# FMB-MCU.net
KiCad netlist of a schematic drawn in Altium Designer
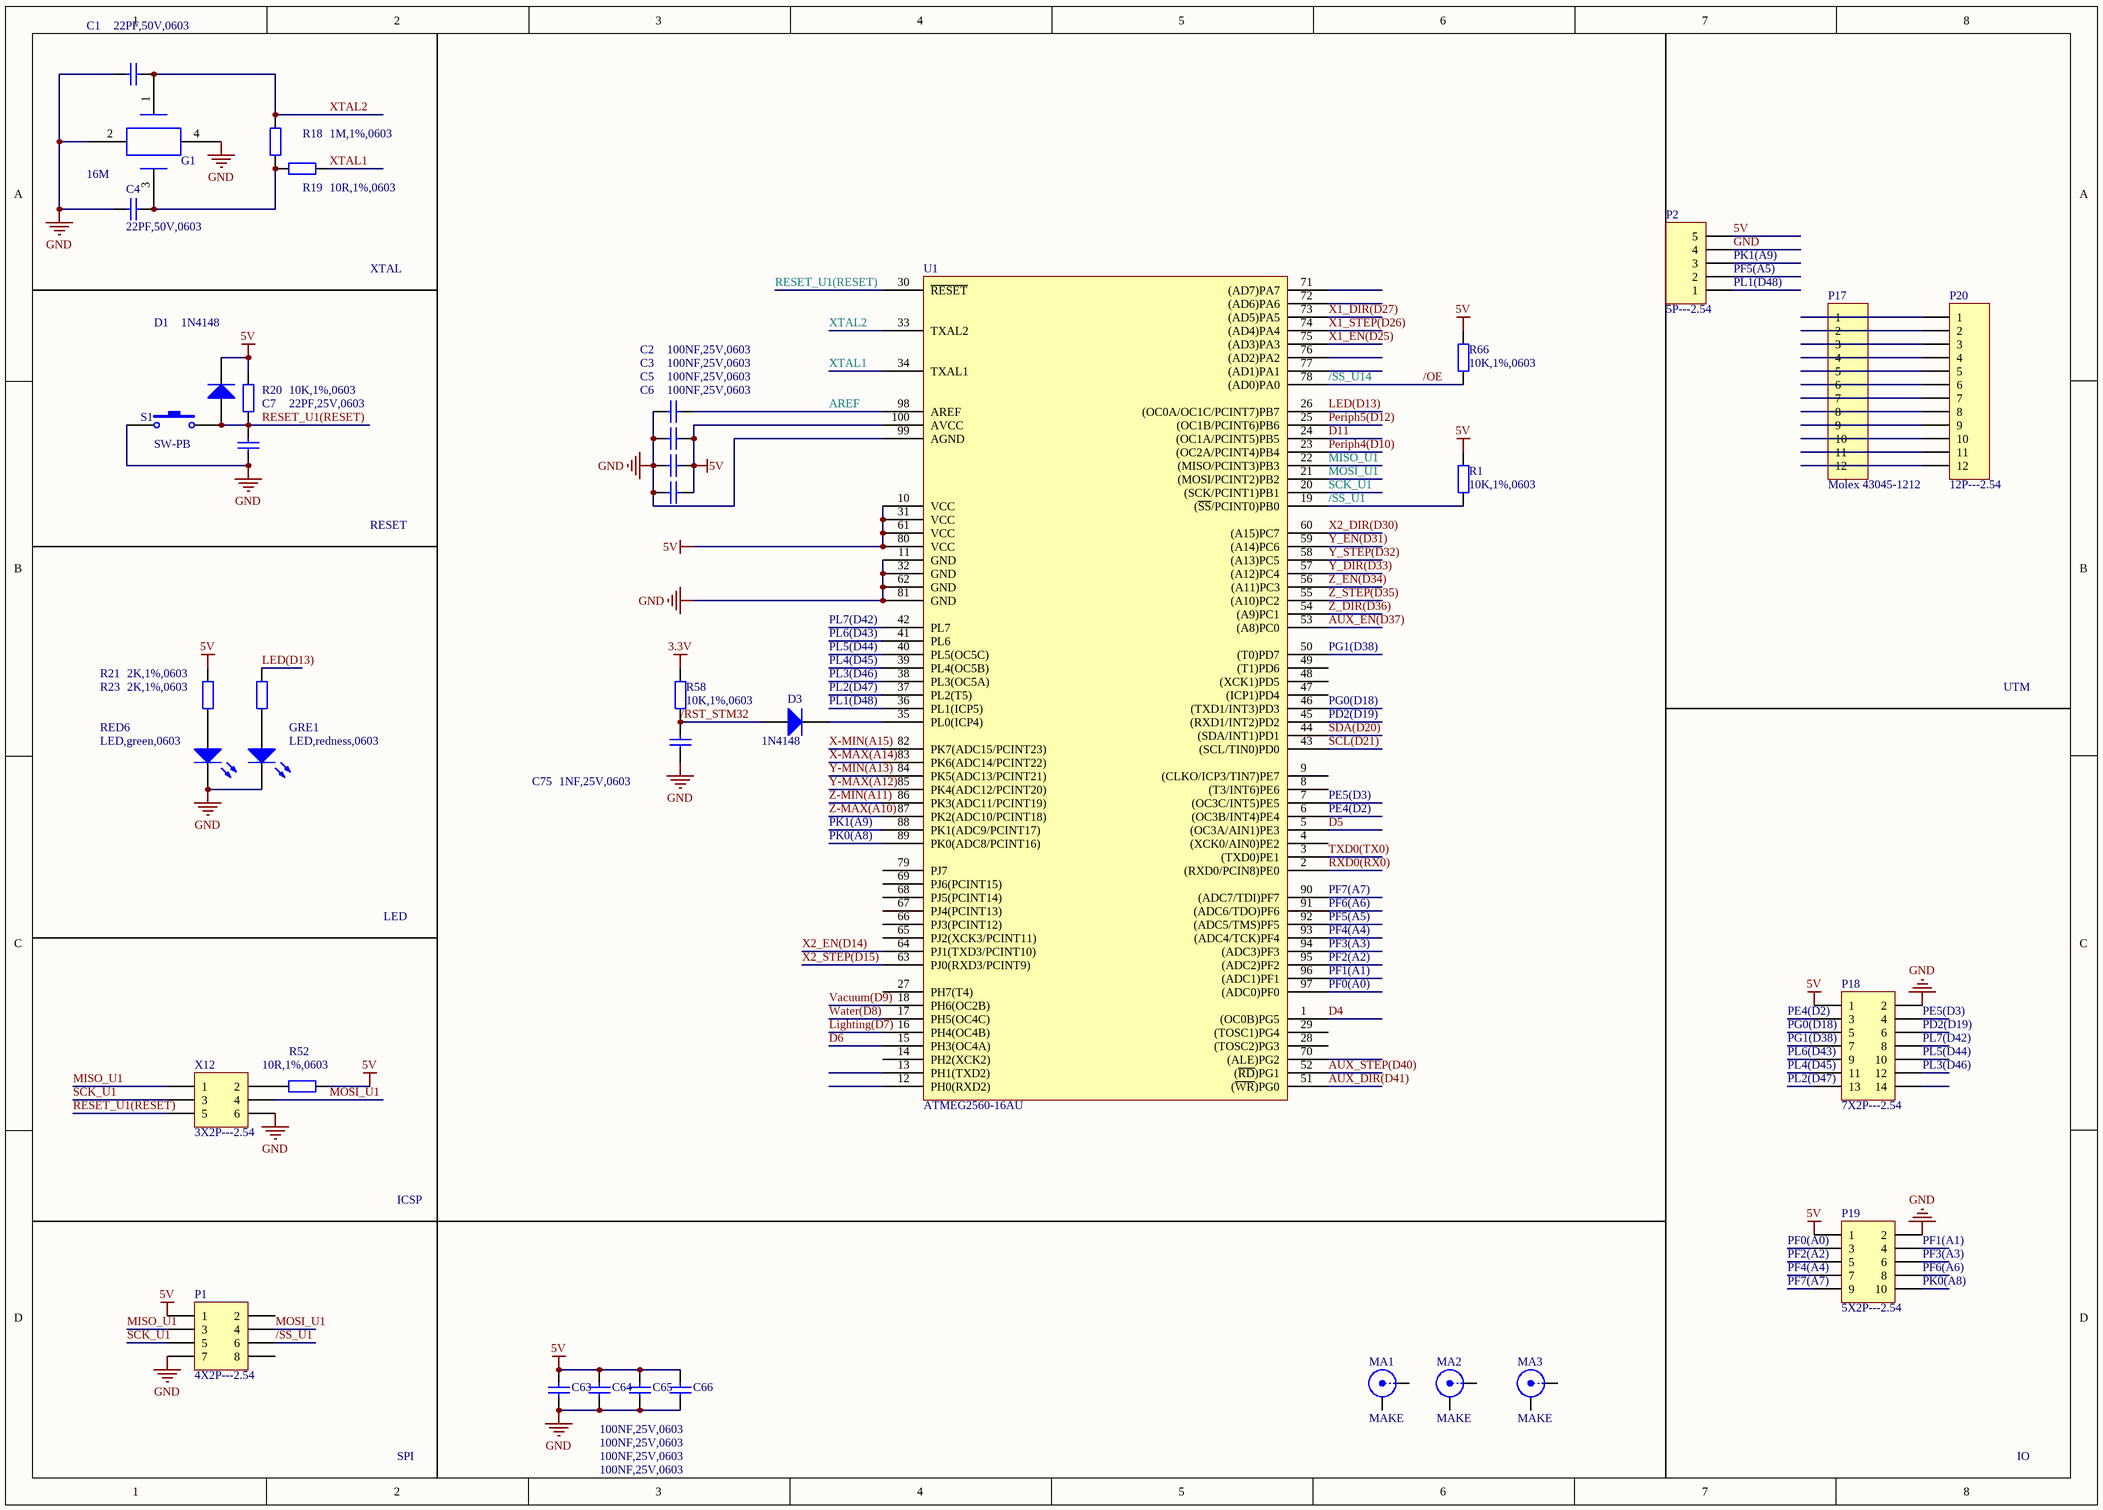
[diagram p0: FMB-MCU.SchDoc]

(export (version "E")
  (design (tool "Eeschema 10.0.6"))
  (components
    (comp (ref "C1")
      (value "22PF,50V,0603")
      (footprint "RC0603")
      (description "Capacitor")
      (fields (field (name "PUBLISHER") "Altium Limited"))
      (libsource (lib "Miscellaneous Devices") (part "Cap"))
    )
    (comp (ref "C2")
      (value "100NF,25V,0603")
      (footprint "RC0603")
      (description "Capacitor")
      (fields (field (name "PUBLISHER") "Altium Limited"))
      (libsource (lib "Miscellaneous Devices") (part "Cap"))
    )
    (comp (ref "C3")
      (value "100NF,25V,0603")
      (footprint "RC0603")
      (description "Capacitor")
      (fields (field (name "PUBLISHER") "Altium Limited"))
      (libsource (lib "Miscellaneous Devices") (part "Cap"))
    )
    (comp (ref "C4")
      (value "22PF,50V,0603")
      (footprint "RC0603")
      (description "Capacitor")
      (fields (field (name "PUBLISHER") "Altium Limited"))
      (libsource (lib "Miscellaneous Devices") (part "Cap"))
    )
    (comp (ref "C5")
      (value "100NF,25V,0603")
      (footprint "RC0603")
      (description "Capacitor")
      (fields (field (name "PUBLISHER") "Altium Limited"))
      (libsource (lib "Miscellaneous Devices") (part "Cap"))
    )
    (comp (ref "C6")
      (value "100NF,25V,0603")
      (footprint "RC0603")
      (description "Capacitor")
      (fields (field (name "PUBLISHER") "Altium Limited"))
      (libsource (lib "Miscellaneous Devices") (part "Cap"))
    )
    (comp (ref "C7")
      (value "22PF,25V,0603")
      (footprint "RC0603")
      (description "Capacitor")
      (fields (field (name "PUBLISHER") "Altium Limited"))
      (libsource (lib "Miscellaneous Devices") (part "Cap"))
    )
    (comp (ref "C63")
      (value "100NF,25V,0603")
      (footprint "RC0603")
      (description "Capacitor")
      (fields (field (name "PUBLISHER") "Altium Limited"))
      (libsource (lib "Miscellaneous Devices") (part "Cap"))
    )
    (comp (ref "C64")
      (value "100NF,25V,0603")
      (footprint "RC0603")
      (description "Capacitor")
      (fields (field (name "PUBLISHER") "Altium Limited"))
      (libsource (lib "Miscellaneous Devices") (part "Cap"))
    )
    (comp (ref "C65")
      (value "100NF,25V,0603")
      (footprint "RC0603")
      (description "Capacitor")
      (fields (field (name "PUBLISHER") "Altium Limited"))
      (libsource (lib "Miscellaneous Devices") (part "Cap"))
    )
    (comp (ref "C66")
      (value "100NF,25V,0603")
      (footprint "RC0603")
      (description "Capacitor")
      (fields (field (name "PUBLISHER") "Altium Limited"))
      (libsource (lib "Miscellaneous Devices") (part "Cap"))
    )
    (comp (ref "C75")
      (value "1NF,25V,0603")
      (footprint "RC0603")
      (description "Capacitor")
      (fields (field (name "PUBLISHER") "Altium Limited"))
      (libsource (lib "Miscellaneous Devices") (part "Cap"))
    )
    (comp (ref "D1")
      (value "1N4148")
      (footprint "SOD-323")
      (description "Default Diode")
      (fields (field (name "PUBLISHER") "Altium Limited"))
      (libsource (lib "Miscellaneous Devices") (part "Diode"))
    )
    (comp (ref "D3")
      (value "1N4148")
      (footprint "SOD-323")
      (description "Default Diode")
      (fields (field (name "PUBLISHER") "Altium Limited"))
      (libsource (lib "Miscellaneous Devices") (part "Diode"))
    )
    (comp (ref "G1") (value "16M") (footprint "Y-3225") (libsource (lib "STM32F407VE") (part "G")))
    (comp (ref "GRE1")
      (value "LED,redness,0603")
      (footprint "LED-0603")
      (description "Typical INFRARED GaAs LED")
      (fields (field (name "PUBLISHER") "Altium Limited"))
      (libsource (lib "Miscellaneous Devices") (part "LED0"))
    )
    (comp (ref "MA1")
      (value "MAKE")
      (description "BNC Elbow Connector")
      (fields (field (name "PUBLISHER") "Altium Limited"))
      (libsource (lib "Miscellaneous Connectors") (part "BNC"))
    )
    (comp (ref "MA2")
      (value "MAKE")
      (description "BNC Elbow Connector")
      (fields (field (name "PUBLISHER") "Altium Limited"))
      (libsource (lib "Miscellaneous Connectors") (part "BNC"))
    )
    (comp (ref "MA3")
      (value "MAKE")
      (description "BNC Elbow Connector")
      (fields (field (name "PUBLISHER") "Altium Limited"))
      (libsource (lib "Miscellaneous Connectors") (part "BNC"))
    )
    (comp (ref "P1")
      (value "4X2P---2.54")
      (footprint "HDR2X4")
      (description "Header, 4-Pin, Dual row")
      (fields (field (name "PUBLISHER") "Altium Limited"))
      (libsource (lib "Miscellaneous Connectors") (part "Header 4X2"))
    )
    (comp (ref "P2")
      (value "5P---2.54")
      (footprint "HDR1X5")
      (description "Header, 5-Pin")
      (fields (field (name "PUBLISHER") "Altium Limited"))
      (libsource (lib "Miscellaneous Connectors") (part "Header 5"))
    )
    (comp (ref "P17")
      (value "Molex 43045-1212")
      (footprint "43045-1212")
      (description "Header, 12-Pin")
      (fields (field (name "PUBLISHER") "Altium Limited"))
      (libsource (lib "Miscellaneous Connectors") (part "Header 12"))
    )
    (comp (ref "P18")
      (value "7X2P---2.54")
      (footprint "HDR2X7")
      (description "Header, 7-Pin, Dual row")
      (fields (field (name "PUBLISHER") "Altium Limited"))
      (libsource (lib "Miscellaneous Connectors") (part "Header 7X2"))
    )
    (comp (ref "P19")
      (value "5X2P---2.54")
      (footprint "HDR2X5")
      (description "Header, 5-Pin, Dual row")
      (fields (field (name "PUBLISHER") "Altium Limited"))
      (libsource (lib "Miscellaneous Connectors") (part "Header 5X2"))
    )
    (comp (ref "P20")
      (value "12P---2.54")
      (footprint "HDR1X12")
      (description "Header, 12-Pin")
      (fields (field (name "PUBLISHER") "Altium Limited"))
      (libsource (lib "Miscellaneous Connectors") (part "Header 12"))
    )
    (comp (ref "R1")
      (value "10K,1%,0603")
      (footprint "RC0603")
      (description "Resistor")
      (fields (field (name "PUBLISHER") "Altium Limited"))
      (libsource (lib "") (part "Res2_1"))
    )
    (comp (ref "R18")
      (value "1M,1%,0603")
      (footprint "RC0603")
      (description "Resistor")
      (fields (field (name "PUBLISHER") "Altium Limited"))
      (libsource (lib "Miscellaneous Devices") (part "Res2"))
    )
    (comp (ref "R19")
      (value "10R,1%,0603")
      (footprint "RC0603")
      (description "Resistor")
      (fields (field (name "PUBLISHER") "Altium Limited"))
      (libsource (lib "") (part "Res2_3"))
    )
    (comp (ref "R20")
      (value "10K,1%,0603")
      (footprint "RC0603")
      (description "Resistor")
      (fields (field (name "PUBLISHER") "Altium Limited"))
      (libsource (lib "Miscellaneous Devices") (part "Res2"))
    )
    (comp (ref "R21")
      (value "2K,1%,0603")
      (footprint "RC0603")
      (description "Resistor")
      (fields (field (name "PUBLISHER") "Altium Limited"))
      (libsource (lib "Miscellaneous Devices") (part "Res2"))
    )
    (comp (ref "R23")
      (value "2K,1%,0603")
      (footprint "RC0603")
      (description "Resistor")
      (fields (field (name "PUBLISHER") "Altium Limited"))
      (libsource (lib "Miscellaneous Devices") (part "Res2"))
    )
    (comp (ref "R52")
      (value "10R,1%,0603")
      (footprint "RC0603")
      (description "Resistor")
      (fields (field (name "PUBLISHER") "Altium Limited"))
      (libsource (lib "") (part "Res2_2"))
    )
    (comp (ref "R58")
      (value "10K,1%,0603")
      (footprint "RC0603")
      (description "Resistor")
      (fields (field (name "PUBLISHER") "Altium Limited"))
      (libsource (lib "Miscellaneous Devices") (part "Res2"))
    )
    (comp (ref "R66")
      (value "10K,1%,0603")
      (footprint "RC0603")
      (description "Resistor")
      (fields (field (name "PUBLISHER") "Altium Limited"))
      (libsource (lib "") (part "Res2_1"))
    )
    (comp (ref "RED6")
      (value "LED,green,0603")
      (footprint "LED-0603")
      (description "Typical INFRARED GaAs LED")
      (fields (field (name "PUBLISHER") "Altium Limited"))
      (libsource (lib "Miscellaneous Devices") (part "LED0"))
    )
    (comp (ref "S1")
      (value "SW-PB")
      (footprint "DIP6*6")
      (description "Switch")
      (fields (field (name "PUBLISHER") "Altium Limited"))
      (libsource (lib "Miscellaneous Devices") (part "SW-PB"))
    )
    (comp (ref "U1")
      (value "ATMEG2560-16AU")
      (footprint "LQFP-100")
      (libsource (lib "LDO原理图库") (part "ATMEG2560-16AU"))
    )
    (comp (ref "X12")
      (value "3X2P---2.54")
      (footprint "HDR2X3")
      (description "Header, 3-Pin, Dual row")
      (fields (field (name "PUBLISHER") "Altium Limited"))
      (libsource (lib "Miscellaneous Connectors") (part "Header 3X2"))
    )
  )
  (nets
    (net (code "1") (name "/AREF") (class "Default")
      (node (ref "C2") (pin "1") (pinfunction "1_1") (pintype "passive"))
      (node (ref "U1") (pin "98") (pinfunction "AREF_98") (pintype "passive"))
    )
    (net (code "2") (name "/AUX_DIR(D41)") (class "Default")
      (node (ref "U1") (pin "51") (pinfunction "(~{WR})PG0_51") (pintype "passive"))
    )
    (net (code "3") (name "/AUX_EN(D37)") (class "Default")
      (node (ref "U1") (pin "53") (pinfunction "(A8)PC0_53") (pintype "passive"))
    )
    (net (code "4") (name "/AUX_STEP(D40)") (class "Default")
      (node (ref "U1") (pin "52") (pinfunction "(~{RD})PG1_52") (pintype "passive"))
    )
    (net (code "5") (name "/D4") (class "Default")
      (node (ref "U1") (pin "1") (pinfunction "(OC0B)PG5_1") (pintype "passive"))
    )
    (net (code "6") (name "/D5") (class "Default")
      (node (ref "U1") (pin "5") (pinfunction "(OC3A/AIN1)PE3_5") (pintype "passive"))
    )
    (net (code "7") (name "/D6") (class "Default")
      (node (ref "U1") (pin "15") (pinfunction "PH3(OC4A)_15") (pintype "passive"))
    )
    (net (code "8") (name "/D11") (class "Default")
      (node (ref "U1") (pin "24") (pinfunction "(OC1A/PCINT5)PB5_24") (pintype "passive"))
    )
    (net (code "9") (name "/LED(D13)") (class "Default")
      (node (ref "R21") (pin "1") (pinfunction "1_1") (pintype "passive"))
      (node (ref "U1") (pin "26") (pinfunction "(OC0A/OC1C/PCINT7)PB7_26") (pintype "passive"))
    )
    (net (code "10") (name "/Lighting(D7)") (class "Default")
      (node (ref "U1") (pin "16") (pinfunction "PH4(OC4B)_16") (pintype "passive"))
    )
    (net (code "11") (name "/MISO_U1") (class "Default")
      (node (ref "P1") (pin "3") (pinfunction "3_3") (pintype "passive"))
      (node (ref "U1") (pin "22") (pinfunction "(MISO/PCINT3)PB3_22") (pintype "passive"))
      (node (ref "X12") (pin "1") (pinfunction "1_1") (pintype "passive"))
    )
    (net (code "12") (name "/MOSI_U1") (class "Default")
      (node (ref "P1") (pin "4") (pinfunction "4_4") (pintype "passive"))
      (node (ref "U1") (pin "21") (pinfunction "(MOSI/PCINT2)PB2_21") (pintype "passive"))
      (node (ref "X12") (pin "4") (pinfunction "4_4") (pintype "passive"))
    )
    (net (code "13") (name "/PD2(D19)") (class "Default")
      (node (ref "P18") (pin "6") (pinfunction "6_6") (pintype "passive"))
      (node (ref "U1") (pin "45") (pinfunction "(RXD1/INT2)PD2_45") (pintype "passive"))
    )
    (net (code "14") (name "/PE4(D2)") (class "Default")
      (node (ref "P18") (pin "3") (pinfunction "3_3") (pintype "passive"))
      (node (ref "U1") (pin "6") (pinfunction "(OC3B/INT4)PE4_6") (pintype "passive"))
    )
    (net (code "15") (name "/PE5(D3)") (class "Default")
      (node (ref "P18") (pin "4") (pinfunction "4_4") (pintype "passive"))
      (node (ref "U1") (pin "7") (pinfunction "(OC3C/INT5)PE5_7") (pintype "passive"))
    )
    (net (code "16") (name "/PF0(A0)") (class "Default")
      (node (ref "P19") (pin "3") (pinfunction "3_3") (pintype "passive"))
      (node (ref "U1") (pin "97") (pinfunction "(ADC0)PF0_97") (pintype "passive"))
    )
    (net (code "17") (name "/PF1(A1)") (class "Default")
      (node (ref "P19") (pin "4") (pinfunction "4_4") (pintype "passive"))
      (node (ref "U1") (pin "96") (pinfunction "(ADC1)PF1_96") (pintype "passive"))
    )
    (net (code "18") (name "/PF2(A2)") (class "Default")
      (node (ref "P19") (pin "5") (pinfunction "5_5") (pintype "passive"))
      (node (ref "U1") (pin "95") (pinfunction "(ADC2)PF2_95") (pintype "passive"))
    )
    (net (code "19") (name "/PF3(A3)") (class "Default")
      (node (ref "P19") (pin "6") (pinfunction "6_6") (pintype "passive"))
      (node (ref "U1") (pin "94") (pinfunction "(ADC3)PF3_94") (pintype "passive"))
    )
    (net (code "20") (name "/PF4(A4)") (class "Default")
      (node (ref "P19") (pin "7") (pinfunction "7_7") (pintype "passive"))
      (node (ref "U1") (pin "93") (pinfunction "(ADC4/TCK)PF4_93") (pintype "passive"))
    )
    (net (code "21") (name "/PF5(A5)") (class "Default")
      (node (ref "P2") (pin "2") (pinfunction "2_2") (pintype "passive"))
      (node (ref "U1") (pin "92") (pinfunction "(ADC5/TMS)PF5_92") (pintype "passive"))
    )
    (net (code "22") (name "/PF6(A6)") (class "Default")
      (node (ref "P19") (pin "8") (pinfunction "8_8") (pintype "passive"))
      (node (ref "U1") (pin "91") (pinfunction "(ADC6/TDO)PF6_91") (pintype "passive"))
    )
    (net (code "23") (name "/PF7(A7)") (class "Default")
      (node (ref "P19") (pin "9") (pinfunction "9_9") (pintype "passive"))
      (node (ref "U1") (pin "90") (pinfunction "(ADC7/TDI)PF7_90") (pintype "passive"))
    )
    (net (code "24") (name "/PG0(D18)") (class "Default")
      (node (ref "P18") (pin "5") (pinfunction "5_5") (pintype "passive"))
      (node (ref "U1") (pin "46") (pinfunction "(TXD1/INT3)PD3_46") (pintype "passive"))
    )
    (net (code "25") (name "/PG1(D38)") (class "Default")
      (node (ref "P18") (pin "7") (pinfunction "7_7") (pintype "passive"))
      (node (ref "U1") (pin "50") (pinfunction "(T0)PD7_50") (pintype "passive"))
    )
    (net (code "26") (name "/PK0(A8)") (class "Default")
      (node (ref "P19") (pin "10") (pinfunction "10_10") (pintype "passive"))
      (node (ref "U1") (pin "89") (pinfunction "PK0(ADC8/PCINT16)_89") (pintype "passive"))
    )
    (net (code "27") (name "/PK1(A9)") (class "Default")
      (node (ref "P2") (pin "3") (pinfunction "3_3") (pintype "passive"))
      (node (ref "U1") (pin "88") (pinfunction "PK1(ADC9/PCINT17)_88") (pintype "passive"))
    )
    (net (code "28") (name "/PL1(D48)") (class "Default")
      (node (ref "P2") (pin "1") (pinfunction "1_1") (pintype "passive"))
      (node (ref "U1") (pin "36") (pinfunction "PL1(ICP5)_36") (pintype "passive"))
    )
    (net (code "29") (name "/PL2(D47)") (class "Default")
      (node (ref "P18") (pin "13") (pinfunction "13_13") (pintype "passive"))
      (node (ref "U1") (pin "37") (pinfunction "PL2(T5)_37") (pintype "passive"))
    )
    (net (code "30") (name "/PL3(D46)") (class "Default")
      (node (ref "P18") (pin "12") (pinfunction "12_12") (pintype "passive"))
      (node (ref "U1") (pin "38") (pinfunction "PL3(OC5A)_38") (pintype "passive"))
    )
    (net (code "31") (name "/PL4(D45)") (class "Default")
      (node (ref "P18") (pin "11") (pinfunction "11_11") (pintype "passive"))
      (node (ref "U1") (pin "39") (pinfunction "PL4(OC5B)_39") (pintype "passive"))
    )
    (net (code "32") (name "/PL5(D44)") (class "Default")
      (node (ref "P18") (pin "10") (pinfunction "10_10") (pintype "passive"))
      (node (ref "U1") (pin "40") (pinfunction "PL5(OC5C)_40") (pintype "passive"))
    )
    (net (code "33") (name "/PL6(D43)") (class "Default")
      (node (ref "P18") (pin "9") (pinfunction "9_9") (pintype "passive"))
      (node (ref "U1") (pin "41") (pinfunction "PL6_41") (pintype "passive"))
    )
    (net (code "34") (name "/PL7(D42)") (class "Default")
      (node (ref "P18") (pin "8") (pinfunction "8_8") (pintype "passive"))
      (node (ref "U1") (pin "42") (pinfunction "PL7_42") (pintype "passive"))
    )
    (net (code "35") (name "/Periph4(D10)") (class "Default")
      (node (ref "U1") (pin "23") (pinfunction "(OC2A/PCINT4)PB4_23") (pintype "passive"))
    )
    (net (code "36") (name "/Periph5(D12)") (class "Default")
      (node (ref "U1") (pin "25") (pinfunction "(OC1B/PCINT6)PB6_25") (pintype "passive"))
    )
    (net (code "37") (name "/RESET_U1(RESET)") (class "Default")
      (node (ref "C7") (pin "1") (pinfunction "1_1") (pintype "passive"))
      (node (ref "D1") (pin "1") (pinfunction "A_1") (pintype "passive"))
      (node (ref "R20") (pin "2") (pinfunction "2_2") (pintype "passive"))
      (node (ref "S1") (pin "2") (pinfunction "2_2") (pintype "passive"))
      (node (ref "U1") (pin "30") (pinfunction "~{RESET}_30") (pintype "passive"))
      (node (ref "X12") (pin "5") (pinfunction "5_5") (pintype "passive"))
    )
    (net (code "38") (name "/RXD0(RX0)") (class "Default")
      (node (ref "U1") (pin "2") (pinfunction "(RXD0/PCIN8)PE0_2") (pintype "passive"))
    )
    (net (code "39") (name "/SCK_U1") (class "Default")
      (node (ref "P1") (pin "5") (pinfunction "5_5") (pintype "passive"))
      (node (ref "U1") (pin "20") (pinfunction "(SCK/PCINT1)PB1_20") (pintype "passive"))
      (node (ref "X12") (pin "3") (pinfunction "3_3") (pintype "passive"))
    )
    (net (code "40") (name "/SCL(D21)") (class "Default")
      (node (ref "U1") (pin "43") (pinfunction "(SCL/TIN0)PD0_43") (pintype "passive"))
    )
    (net (code "41") (name "/SDA(D20)") (class "Default")
      (node (ref "U1") (pin "44") (pinfunction "(SDA/INT1)PD1_44") (pintype "passive"))
    )
    (net (code "42") (name "/TXD0(TX0)") (class "Default")
      (node (ref "U1") (pin "3") (pinfunction "(TXD0)PE1_3") (pintype "passive"))
    )
    (net (code "43") (name "/Vacuum(D9)") (class "Default")
      (node (ref "U1") (pin "18") (pinfunction "PH6(OC2B)_18") (pintype "passive"))
    )
    (net (code "44") (name "/Water(D8)") (class "Default")
      (node (ref "U1") (pin "17") (pinfunction "PH5(OC4C)_17") (pintype "passive"))
    )
    (net (code "45") (name "/X-MAX(A14)") (class "Default")
      (node (ref "U1") (pin "83") (pinfunction "PK6(ADC14/PCINT22)_83") (pintype "passive"))
    )
    (net (code "46") (name "/X-MIN(A15)") (class "Default")
      (node (ref "U1") (pin "82") (pinfunction "PK7(ADC15/PCINT23)_82") (pintype "passive"))
    )
    (net (code "47") (name "/X1_DIR(D27)") (class "Default")
      (node (ref "U1") (pin "73") (pinfunction "(AD5)PA5_73") (pintype "passive"))
    )
    (net (code "48") (name "/X1_EN(D25)") (class "Default")
      (node (ref "U1") (pin "75") (pinfunction "(AD3)PA3_75") (pintype "passive"))
    )
    (net (code "49") (name "/X1_STEP(D26)") (class "Default")
      (node (ref "U1") (pin "74") (pinfunction "(AD4)PA4_74") (pintype "passive"))
    )
    (net (code "50") (name "/X2_DIR(D30)") (class "Default")
      (node (ref "U1") (pin "60") (pinfunction "(A15)PC7_60") (pintype "passive"))
    )
    (net (code "51") (name "/X2_EN(D14)") (class "Default")
      (node (ref "U1") (pin "64") (pinfunction "PJ1(TXD3/PCINT10)_64") (pintype "passive"))
    )
    (net (code "52") (name "/X2_STEP(D15)") (class "Default")
      (node (ref "U1") (pin "63") (pinfunction "PJ0(RXD3/PCINT9)_63") (pintype "passive"))
    )
    (net (code "53") (name "/XTAL1") (class "Default")
      (node (ref "R19") (pin "2") (pinfunction "2_2") (pintype "passive"))
      (node (ref "U1") (pin "34") (pinfunction "TXAL1_34") (pintype "passive"))
    )
    (net (code "54") (name "/XTAL2") (class "Default")
      (node (ref "C1") (pin "1") (pinfunction "1_1") (pintype "passive"))
      (node (ref "G1") (pin "1") (pintype "passive"))
      (node (ref "R18") (pin "1") (pinfunction "1_1") (pintype "passive"))
      (node (ref "U1") (pin "33") (pinfunction "TXAL2_33") (pintype "passive"))
    )
    (net (code "55") (name "/Y-MAX(A12)") (class "Default")
      (node (ref "U1") (pin "85") (pinfunction "PK4(ADC12/PCINT20)_85") (pintype "passive"))
    )
    (net (code "56") (name "/Y-MIN(A13)") (class "Default")
      (node (ref "U1") (pin "84") (pinfunction "PK5(ADC13/PCINT21)_84") (pintype "passive"))
    )
    (net (code "57") (name "/Y_DIR(D33)") (class "Default")
      (node (ref "U1") (pin "57") (pinfunction "(A12)PC4_57") (pintype "passive"))
    )
    (net (code "58") (name "/Y_EN(D31)") (class "Default")
      (node (ref "U1") (pin "59") (pinfunction "(A14)PC6_59") (pintype "passive"))
    )
    (net (code "59") (name "/Y_STEP(D32)") (class "Default")
      (node (ref "U1") (pin "58") (pinfunction "(A13)PC5_58") (pintype "passive"))
    )
    (net (code "60") (name "/Z-MAX(A10)") (class "Default")
      (node (ref "U1") (pin "87") (pinfunction "PK2(ADC10/PCINT18)_87") (pintype "passive"))
    )
    (net (code "61") (name "/Z-MIN(A11)") (class "Default")
      (node (ref "U1") (pin "86") (pinfunction "PK3(ADC11/PCINT19)_86") (pintype "passive"))
    )
    (net (code "62") (name "/Z_DIR(D36)") (class "Default")
      (node (ref "U1") (pin "54") (pinfunction "(A9)PC1_54") (pintype "passive"))
    )
    (net (code "63") (name "/Z_EN(D34)") (class "Default")
      (node (ref "U1") (pin "56") (pinfunction "(A11)PC3_56") (pintype "passive"))
    )
    (net (code "64") (name "/Z_STEP(D35)") (class "Default")
      (node (ref "U1") (pin "55") (pinfunction "(A10)PC2_55") (pintype "passive"))
    )
    (net (code "65") (name "/{slash}OE") (class "Default")
      (node (ref "R66") (pin "1") (pinfunction "1_1") (pintype "passive"))
      (node (ref "U1") (pin "78") (pinfunction "(AD0)PA0_78") (pintype "passive"))
    )
    (net (code "66") (name "/{slash}RST_STM32") (class "Default")
      (node (ref "C75") (pin "2") (pinfunction "2_2") (pintype "passive"))
      (node (ref "D3") (pin "1") (pinfunction "A_1") (pintype "passive"))
      (node (ref "R58") (pin "2") (pinfunction "2_2") (pintype "passive"))
    )
    (net (code "67") (name "/{slash}SS_U1") (class "Default")
      (node (ref "P1") (pin "6") (pinfunction "6_6") (pintype "passive"))
      (node (ref "R1") (pin "1") (pinfunction "1_1") (pintype "passive"))
      (node (ref "U1") (pin "19") (pinfunction "(~{SS}/PCINT0)PB0_19") (pintype "passive"))
    )
    (net (code "68") (name "3.3V") (class "Default")
      (node (ref "R58") (pin "1") (pinfunction "1_1") (pintype "passive"))
    )
    (net (code "69") (name "5V") (class "Default")
      (node (ref "C3") (pin "1") (pinfunction "1_1") (pintype "passive"))
      (node (ref "C5") (pin "1") (pinfunction "1_1") (pintype "passive"))
      (node (ref "C6") (pin "1") (pinfunction "1_1") (pintype "passive"))
      (node (ref "C63") (pin "1") (pinfunction "1_1") (pintype "passive"))
      (node (ref "C64") (pin "1") (pinfunction "1_1") (pintype "passive"))
      (node (ref "C65") (pin "1") (pinfunction "1_1") (pintype "passive"))
      (node (ref "C66") (pin "1") (pinfunction "1_1") (pintype "passive"))
      (node (ref "D1") (pin "2") (pinfunction "K_2") (pintype "passive"))
      (node (ref "P1") (pin "1") (pinfunction "1_1") (pintype "passive"))
      (node (ref "P18") (pin "1") (pinfunction "1_1") (pintype "passive"))
      (node (ref "P19") (pin "1") (pinfunction "1_1") (pintype "passive"))
      (node (ref "P2") (pin "5") (pinfunction "5_5") (pintype "passive"))
      (node (ref "R1") (pin "2") (pinfunction "2_2") (pintype "passive"))
      (node (ref "R20") (pin "1") (pinfunction "1_1") (pintype "passive"))
      (node (ref "R23") (pin "1") (pinfunction "1_1") (pintype "passive"))
      (node (ref "R52") (pin "1") (pinfunction "1_1") (pintype "passive"))
      (node (ref "R66") (pin "2") (pinfunction "2_2") (pintype "passive"))
      (node (ref "U1") (pin "10") (pinfunction "VCC_10") (pintype "passive"))
      (node (ref "U1") (pin "100") (pinfunction "AVCC_100") (pintype "passive"))
      (node (ref "U1") (pin "31") (pinfunction "VCC_31") (pintype "passive"))
      (node (ref "U1") (pin "61") (pinfunction "VCC_61") (pintype "passive"))
      (node (ref "U1") (pin "80") (pinfunction "VCC_80") (pintype "passive"))
    )
    (net (code "70") (name "GND") (class "Default")
      (node (ref "C1") (pin "2") (pinfunction "2_2") (pintype "passive"))
      (node (ref "C2") (pin "2") (pinfunction "2_2") (pintype "passive"))
      (node (ref "C3") (pin "2") (pinfunction "2_2") (pintype "passive"))
      (node (ref "C4") (pin "1") (pinfunction "1_1") (pintype "passive"))
      (node (ref "C5") (pin "2") (pinfunction "2_2") (pintype "passive"))
      (node (ref "C6") (pin "2") (pinfunction "2_2") (pintype "passive"))
      (node (ref "C63") (pin "2") (pinfunction "2_2") (pintype "passive"))
      (node (ref "C64") (pin "2") (pinfunction "2_2") (pintype "passive"))
      (node (ref "C65") (pin "2") (pinfunction "2_2") (pintype "passive"))
      (node (ref "C66") (pin "2") (pinfunction "2_2") (pintype "passive"))
      (node (ref "C7") (pin "2") (pinfunction "2_2") (pintype "passive"))
      (node (ref "C75") (pin "1") (pinfunction "1_1") (pintype "passive"))
      (node (ref "G1") (pin "2") (pintype "passive"))
      (node (ref "G1") (pin "4") (pintype "passive"))
      (node (ref "GRE1") (pin "2") (pinfunction "K_2") (pintype "passive"))
      (node (ref "P1") (pin "7") (pinfunction "7_7") (pintype "passive"))
      (node (ref "P18") (pin "2") (pinfunction "2_2") (pintype "passive"))
      (node (ref "P19") (pin "2") (pinfunction "2_2") (pintype "passive"))
      (node (ref "P2") (pin "4") (pinfunction "4_4") (pintype "passive"))
      (node (ref "RED6") (pin "2") (pinfunction "K_2") (pintype "passive"))
      (node (ref "S1") (pin "1") (pinfunction "1_1") (pintype "passive"))
      (node (ref "U1") (pin "11") (pinfunction "GND_11") (pintype "passive"))
      (node (ref "U1") (pin "32") (pinfunction "GND_32") (pintype "passive"))
      (node (ref "U1") (pin "62") (pinfunction "GND_62") (pintype "passive"))
      (node (ref "U1") (pin "81") (pinfunction "GND_81") (pintype "passive"))
      (node (ref "U1") (pin "99") (pinfunction "AGND_99") (pintype "passive"))
      (node (ref "X12") (pin "6") (pinfunction "6_6") (pintype "passive"))
    )
    (net (code "71") (name "Net-(C4-Pad2)") (class "Default")
      (node (ref "C4") (pin "2") (pinfunction "2_2") (pintype "passive"))
      (node (ref "G1") (pin "3") (pintype "passive"))
      (node (ref "R18") (pin "2") (pinfunction "2_2") (pintype "passive"))
      (node (ref "R19") (pin "1") (pinfunction "1_1") (pintype "passive"))
    )
    (net (code "72") (name "Net-(D3-K)") (class "Default")
      (node (ref "D3") (pin "2") (pinfunction "K_2") (pintype "passive"))
      (node (ref "U1") (pin "35") (pinfunction "PL0(ICP4)_35") (pintype "passive"))
    )
    (net (code "73") (name "Net-(GRE1-A)") (class "Default")
      (node (ref "GRE1") (pin "1") (pinfunction "A_1") (pintype "passive"))
      (node (ref "R21") (pin "2") (pinfunction "2_2") (pintype "passive"))
    )
    (net (code "74") (name "Net-(P17-Pad1)") (class "Default")
      (node (ref "P17") (pin "1") (pinfunction "1_1") (pintype "passive"))
      (node (ref "P20") (pin "1") (pinfunction "1_1") (pintype "passive"))
    )
    (net (code "75") (name "Net-(P17-Pad2)") (class "Default")
      (node (ref "P17") (pin "2") (pinfunction "2_2") (pintype "passive"))
      (node (ref "P20") (pin "2") (pinfunction "2_2") (pintype "passive"))
    )
    (net (code "76") (name "Net-(P17-Pad3)") (class "Default")
      (node (ref "P17") (pin "3") (pinfunction "3_3") (pintype "passive"))
      (node (ref "P20") (pin "3") (pinfunction "3_3") (pintype "passive"))
    )
    (net (code "77") (name "Net-(P17-Pad4)") (class "Default")
      (node (ref "P17") (pin "4") (pinfunction "4_4") (pintype "passive"))
      (node (ref "P20") (pin "4") (pinfunction "4_4") (pintype "passive"))
    )
    (net (code "78") (name "Net-(P17-Pad5)") (class "Default")
      (node (ref "P17") (pin "5") (pinfunction "5_5") (pintype "passive"))
      (node (ref "P20") (pin "5") (pinfunction "5_5") (pintype "passive"))
    )
    (net (code "79") (name "Net-(P17-Pad6)") (class "Default")
      (node (ref "P17") (pin "6") (pinfunction "6_6") (pintype "passive"))
      (node (ref "P20") (pin "6") (pinfunction "6_6") (pintype "passive"))
    )
    (net (code "80") (name "Net-(P17-Pad7)") (class "Default")
      (node (ref "P17") (pin "7") (pinfunction "7_7") (pintype "passive"))
      (node (ref "P20") (pin "7") (pinfunction "7_7") (pintype "passive"))
    )
    (net (code "81") (name "Net-(P17-Pad8)") (class "Default")
      (node (ref "P17") (pin "8") (pinfunction "8_8") (pintype "passive"))
      (node (ref "P20") (pin "8") (pinfunction "8_8") (pintype "passive"))
    )
    (net (code "82") (name "Net-(P17-Pad9)") (class "Default")
      (node (ref "P17") (pin "9") (pinfunction "9_9") (pintype "passive"))
      (node (ref "P20") (pin "9") (pinfunction "9_9") (pintype "passive"))
    )
    (net (code "83") (name "Net-(P17-Pad10)") (class "Default")
      (node (ref "P17") (pin "10") (pinfunction "10_10") (pintype "passive"))
      (node (ref "P20") (pin "10") (pinfunction "10_10") (pintype "passive"))
    )
    (net (code "84") (name "Net-(P17-Pad11)") (class "Default")
      (node (ref "P17") (pin "11") (pinfunction "11_11") (pintype "passive"))
      (node (ref "P20") (pin "11") (pinfunction "11_11") (pintype "passive"))
    )
    (net (code "85") (name "Net-(P17-Pad12)") (class "Default")
      (node (ref "P17") (pin "12") (pinfunction "12_12") (pintype "passive"))
      (node (ref "P20") (pin "12") (pinfunction "12_12") (pintype "passive"))
    )
    (net (code "86") (name "Net-(R52-Pad2)") (class "Default")
      (node (ref "R52") (pin "2") (pinfunction "2_2") (pintype "passive"))
      (node (ref "X12") (pin "2") (pinfunction "2_2") (pintype "passive"))
    )
    (net (code "87") (name "Net-(RED6-A)") (class "Default")
      (node (ref "R23") (pin "2") (pinfunction "2_2") (pintype "passive"))
      (node (ref "RED6") (pin "1") (pinfunction "A_1") (pintype "passive"))
    )
    (net (code "88") (name "unconnected-(MA1-X-Pad1)") (class "Default")
      (node (ref "MA1") (pin "1") (pinfunction "X_1") (pintype "passive"))
    )
    (net (code "89") (name "unconnected-(MA1-Y-Pad2)") (class "Default")
      (node (ref "MA1") (pin "2") (pinfunction "Y_2") (pintype "passive"))
    )
    (net (code "90") (name "unconnected-(MA2-X-Pad1)") (class "Default")
      (node (ref "MA2") (pin "1") (pinfunction "X_1") (pintype "passive"))
    )
    (net (code "91") (name "unconnected-(MA2-Y-Pad2)") (class "Default")
      (node (ref "MA2") (pin "2") (pinfunction "Y_2") (pintype "passive"))
    )
    (net (code "92") (name "unconnected-(MA3-X-Pad1)") (class "Default")
      (node (ref "MA3") (pin "1") (pinfunction "X_1") (pintype "passive"))
    )
    (net (code "93") (name "unconnected-(MA3-Y-Pad2)") (class "Default")
      (node (ref "MA3") (pin "2") (pinfunction "Y_2") (pintype "passive"))
    )
    (net (code "94") (name "unconnected-(P1-Pad2)") (class "Default")
      (node (ref "P1") (pin "2") (pinfunction "2_2") (pintype "passive"))
    )
    (net (code "95") (name "unconnected-(P1-Pad8)") (class "Default")
      (node (ref "P1") (pin "8") (pinfunction "8_8") (pintype "passive"))
    )
    (net (code "96") (name "unconnected-(P18-Pad14)") (class "Default")
      (node (ref "P18") (pin "14") (pinfunction "14_14") (pintype "passive"))
    )
    (net (code "97") (name "unconnected-(U1-(AD1)PA1-Pad77)") (class "Default")
      (node (ref "U1") (pin "77") (pinfunction "(AD1)PA1_77") (pintype "passive"))
    )
    (net (code "98") (name "unconnected-(U1-(AD2)PA2-Pad76)") (class "Default")
      (node (ref "U1") (pin "76") (pinfunction "(AD2)PA2_76") (pintype "passive"))
    )
    (net (code "99") (name "unconnected-(U1-(AD6)PA6-Pad72)") (class "Default")
      (node (ref "U1") (pin "72") (pinfunction "(AD6)PA6_72") (pintype "passive"))
    )
    (net (code "100") (name "unconnected-(U1-(AD7)PA7-Pad71)") (class "Default")
      (node (ref "U1") (pin "71") (pinfunction "(AD7)PA7_71") (pintype "passive"))
    )
    (net (code "101") (name "unconnected-(U1-(ALE)PG2-Pad70)") (class "Default")
      (node (ref "U1") (pin "70") (pinfunction "(ALE)PG2_70") (pintype "passive"))
    )
    (net (code "102") (name "unconnected-(U1-(CLKO{slash}ICP3{slash}TIN7)PE7-Pad9)") (class "Default")
      (node (ref "U1") (pin "9") (pinfunction "(CLKO/ICP3/TIN7)PE7_9") (pintype "passive"))
    )
    (net (code "103") (name "unconnected-(U1-(ICP1)PD4-Pad47)") (class "Default")
      (node (ref "U1") (pin "47") (pinfunction "(ICP1)PD4_47") (pintype "passive"))
    )
    (net (code "104") (name "unconnected-(U1-(T1)PD6-Pad49)") (class "Default")
      (node (ref "U1") (pin "49") (pinfunction "(T1)PD6_49") (pintype "passive"))
    )
    (net (code "105") (name "unconnected-(U1-(T3{slash}INT6)PE6-Pad8)") (class "Default")
      (node (ref "U1") (pin "8") (pinfunction "(T3/INT6)PE6_8") (pintype "passive"))
    )
    (net (code "106") (name "unconnected-(U1-(TOSC1)PG4-Pad29)") (class "Default")
      (node (ref "U1") (pin "29") (pinfunction "(TOSC1)PG4_29") (pintype "passive"))
    )
    (net (code "107") (name "unconnected-(U1-(TOSC2)PG3-Pad28)") (class "Default")
      (node (ref "U1") (pin "28") (pinfunction "(TOSC2)PG3_28") (pintype "passive"))
    )
    (net (code "108") (name "unconnected-(U1-(XCK0{slash}AIN0)PE2-Pad4)") (class "Default")
      (node (ref "U1") (pin "4") (pinfunction "(XCK0/AIN0)PE2_4") (pintype "passive"))
    )
    (net (code "109") (name "unconnected-(U1-(XCK1)PD5-Pad48)") (class "Default")
      (node (ref "U1") (pin "48") (pinfunction "(XCK1)PD5_48") (pintype "passive"))
    )
    (net (code "110") (name "unconnected-(U1-PH0(RXD2)-Pad12)") (class "Default")
      (node (ref "U1") (pin "12") (pinfunction "PH0(RXD2)_12") (pintype "passive"))
    )
    (net (code "111") (name "unconnected-(U1-PH1(TXD2)-Pad13)") (class "Default")
      (node (ref "U1") (pin "13") (pinfunction "PH1(TXD2)_13") (pintype "passive"))
    )
    (net (code "112") (name "unconnected-(U1-PH2(XCK2)-Pad14)") (class "Default")
      (node (ref "U1") (pin "14") (pinfunction "PH2(XCK2)_14") (pintype "passive"))
    )
    (net (code "113") (name "unconnected-(U1-PH7(T4)-Pad27)") (class "Default")
      (node (ref "U1") (pin "27") (pinfunction "PH7(T4)_27") (pintype "passive"))
    )
    (net (code "114") (name "unconnected-(U1-PJ2(XCK3{slash}PCINT11)-Pad65)") (class "Default")
      (node (ref "U1") (pin "65") (pinfunction "PJ2(XCK3/PCINT11)_65") (pintype "passive"))
    )
    (net (code "115") (name "unconnected-(U1-PJ3(PCINT12)-Pad66)") (class "Default")
      (node (ref "U1") (pin "66") (pinfunction "PJ3(PCINT12)_66") (pintype "passive"))
    )
    (net (code "116") (name "unconnected-(U1-PJ4(PCINT13)-Pad67)") (class "Default")
      (node (ref "U1") (pin "67") (pinfunction "PJ4(PCINT13)_67") (pintype "passive"))
    )
    (net (code "117") (name "unconnected-(U1-PJ5(PCINT14)-Pad68)") (class "Default")
      (node (ref "U1") (pin "68") (pinfunction "PJ5(PCINT14)_68") (pintype "passive"))
    )
    (net (code "118") (name "unconnected-(U1-PJ6(PCINT15)-Pad69)") (class "Default")
      (node (ref "U1") (pin "69") (pinfunction "PJ6(PCINT15)_69") (pintype "passive"))
    )
    (net (code "119") (name "unconnected-(U1-PJ7-Pad79)") (class "Default")
      (node (ref "U1") (pin "79") (pinfunction "PJ7_79") (pintype "passive"))
    )
  )
)
